# PROC051C_LP_Connector.net
KiCad netlist of a schematic drawn in Altium Designer
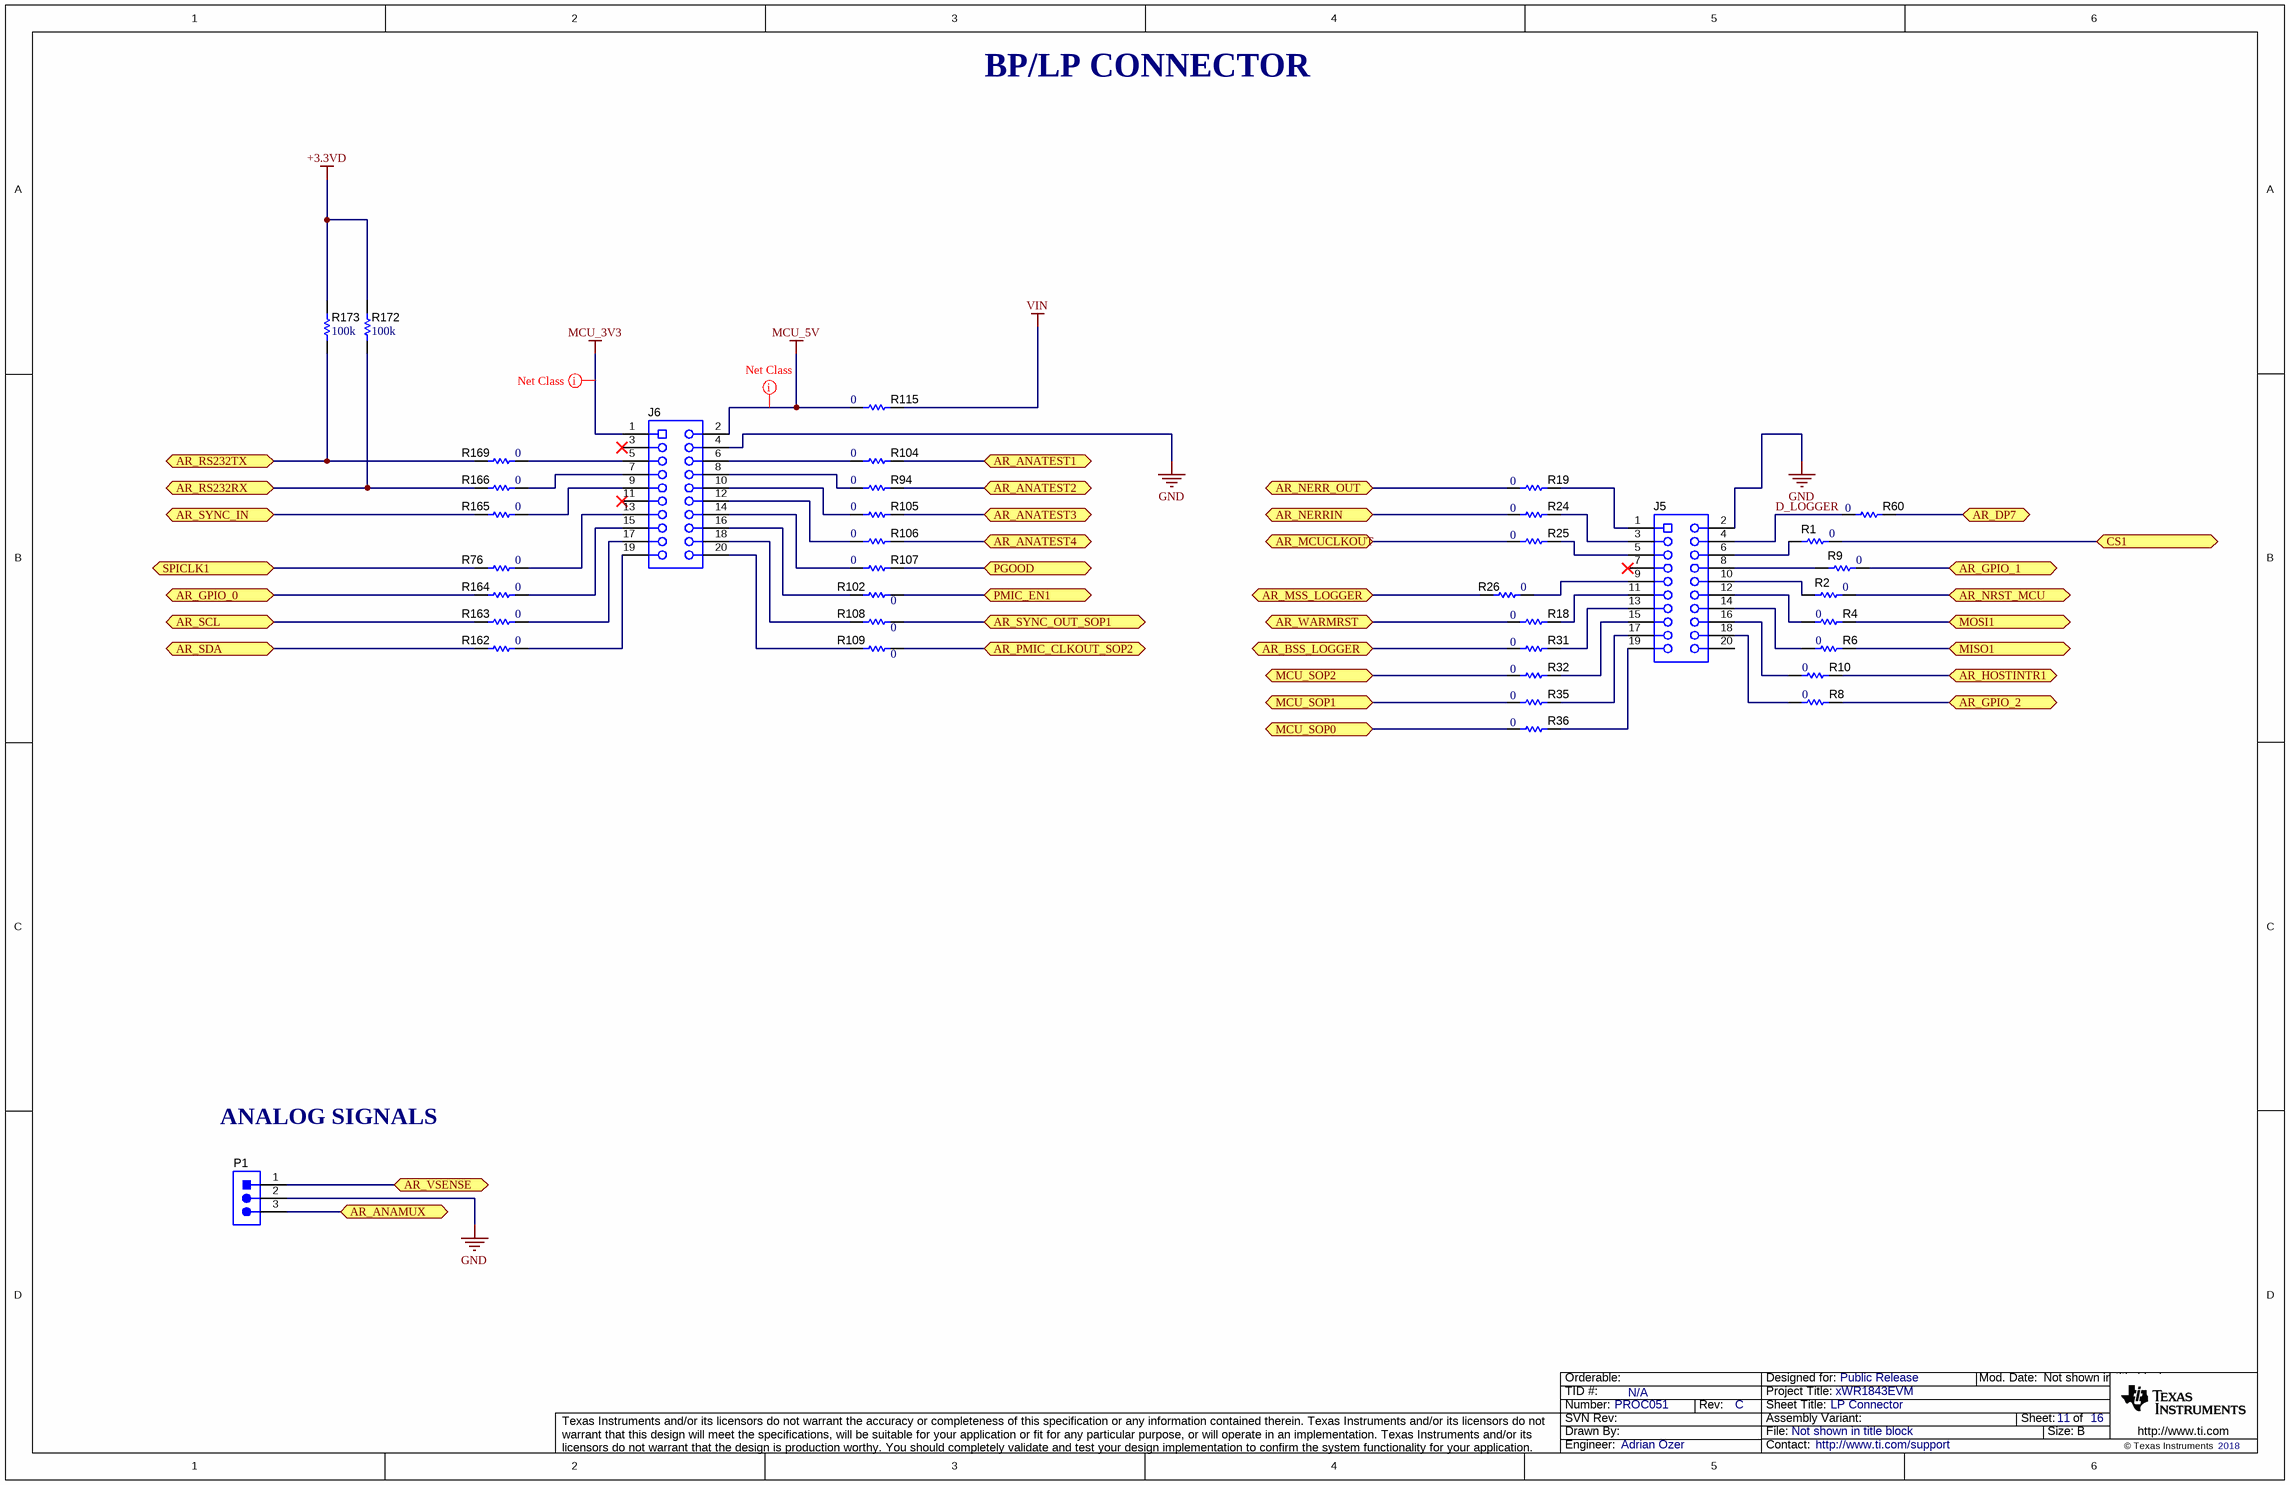
[diagram p0: PROC051C_LP Connector.SchDoc]

(export (version "E")
  (design (tool "Eeschema 10.0.6"))
  (components
    (comp (ref "J5")
      (value "SSM-110-S-DV")
      (footprint "Samtec_SSM-110-x-DV")
      (description "Receptacle, 2.54mm, 10x2, Gold with Tin tail, SMT")
      (fields (field (name "MANUFACTURER") "Samtec"))
      (libsource (lib "Altium Vault - TI") (part "CMP-0078182-1"))
    )
    (comp (ref "J6")
      (value "SSM-110-S-DV")
      (footprint "Samtec_SSM-110-x-DV")
      (description "Receptacle, 2.54mm, 10x2, Gold with Tin tail, SMT")
      (fields (field (name "MANUFACTURER") "Samtec"))
      (libsource (lib "Altium Vault - TI") (part "CMP-0078182-1"))
    )
    (comp (ref "P1")
      (value "TSW-103-07-T-S")
      (footprint "Samtec_TSW-103-07-T-S")
      (description "Header, 2.54 mm, 3x1, Tin, TH")
      (fields (field (name "MANUFACTURER") "Samtec"))
      (libsource (lib "Altium Vault - TI") (part "Header_3x1"))
    )
    (comp (ref "R1")
      (value "CRCW02010000Z0ED")
      (footprint "0201_Silk")
      (description "RES, 0, 5%, 0.05 W, 0201")
      (fields (field (name "MANUFACTURER") "Vishay-Dale") (field (name "VALUEDISPLAYED") "0"))
      (libsource (lib "Altium Vault - TI") (part "Resistor"))
    )
    (comp (ref "R2")
      (value "CRCW02010000Z0ED")
      (footprint "0201_Silk")
      (description "RES, 0, 5%, 0.05 W, 0201")
      (fields (field (name "MANUFACTURER") "Vishay-Dale") (field (name "VALUEDISPLAYED") "0"))
      (libsource (lib "Altium Vault - TI") (part "Resistor"))
    )
    (comp (ref "R4")
      (value "CRCW02010000Z0ED")
      (footprint "0201_Silk")
      (description "RES, 0, 5%, 0.05 W, 0201")
      (fields (field (name "MANUFACTURER") "Vishay-Dale") (field (name "VALUEDISPLAYED") "0"))
      (libsource (lib "Altium Vault - TI") (part "Resistor"))
    )
    (comp (ref "R6")
      (value "CRCW02010000Z0ED")
      (footprint "0201_Silk")
      (description "RES, 0, 5%, 0.05 W, 0201")
      (fields (field (name "MANUFACTURER") "Vishay-Dale") (field (name "VALUEDISPLAYED") "0"))
      (libsource (lib "Altium Vault - TI") (part "Resistor"))
    )
    (comp (ref "R8")
      (value "CRCW02010000Z0ED")
      (footprint "0201_Silk")
      (description "RES, 0, 5%, 0.05 W, 0201")
      (fields (field (name "MANUFACTURER") "Vishay-Dale") (field (name "VALUEDISPLAYED") "0"))
      (libsource (lib "Altium Vault - TI") (part "Resistor"))
    )
    (comp (ref "R9")
      (value "CRCW02010000Z0ED")
      (footprint "0201_Silk")
      (description "RES, 0, 5%, 0.05 W, 0201")
      (fields (field (name "MANUFACTURER") "Vishay-Dale") (field (name "VALUEDISPLAYED") "0"))
      (libsource (lib "Altium Vault - TI") (part "Resistor"))
    )
    (comp (ref "R10")
      (value "CRCW02010000Z0ED")
      (footprint "0201_Silk")
      (description "RES, 0, 5%, 0.05 W, 0201")
      (fields (field (name "MANUFACTURER") "Vishay-Dale") (field (name "VALUEDISPLAYED") "0"))
      (libsource (lib "Altium Vault - TI") (part "Resistor"))
    )
    (comp (ref "R18")
      (value "CRCW02010000Z0ED")
      (footprint "0201_Silk")
      (description "RES, 0, 5%, 0.05 W, 0201")
      (fields (field (name "MANUFACTURER") "Vishay-Dale") (field (name "VALUEDISPLAYED") "0"))
      (libsource (lib "Altium Vault - TI") (part "Resistor"))
    )
    (comp (ref "R19")
      (value "CRCW02010000Z0ED")
      (footprint "0201_Silk")
      (description "RES, 0, 5%, 0.05 W, 0201")
      (fields (field (name "MANUFACTURER") "Vishay-Dale") (field (name "VALUEDISPLAYED") "0"))
      (libsource (lib "Altium Vault - TI") (part "Resistor"))
    )
    (comp (ref "R24")
      (value "CRCW02010000Z0ED")
      (footprint "0201_Silk")
      (description "RES, 0, 5%, 0.05 W, 0201")
      (fields (field (name "MANUFACTURER") "Vishay-Dale") (field (name "VALUEDISPLAYED") "0"))
      (libsource (lib "Altium Vault - TI") (part "Resistor"))
    )
    (comp (ref "R25")
      (value "CRCW02010000Z0ED")
      (footprint "0201_Silk")
      (description "RES, 0, 5%, 0.05 W, 0201")
      (fields (field (name "MANUFACTURER") "Vishay-Dale") (field (name "VALUEDISPLAYED") "0"))
      (libsource (lib "Altium Vault - TI") (part "Resistor"))
    )
    (comp (ref "R26")
      (value "CRCW02010000Z0ED")
      (footprint "0201_Silk")
      (description "RES, 0, 5%, 0.05 W, 0201")
      (fields (field (name "MANUFACTURER") "Vishay-Dale") (field (name "VALUEDISPLAYED") "0"))
      (libsource (lib "Altium Vault - TI") (part "Resistor"))
    )
    (comp (ref "R31")
      (value "CRCW02010000Z0ED")
      (footprint "0201_Silk")
      (description "RES, 0, 5%, 0.05 W, 0201")
      (fields (field (name "MANUFACTURER") "Vishay-Dale") (field (name "VALUEDISPLAYED") "0"))
      (libsource (lib "Altium Vault - TI") (part "Resistor"))
    )
    (comp (ref "R32")
      (value "CRCW02010000Z0ED")
      (footprint "0201_Silk")
      (description "RES, 0, 5%, 0.05 W, 0201")
      (fields (field (name "MANUFACTURER") "Vishay-Dale") (field (name "VALUEDISPLAYED") "0"))
      (libsource (lib "Altium Vault - TI") (part "Resistor"))
    )
    (comp (ref "R35")
      (value "CRCW02010000Z0ED")
      (footprint "0201_Silk")
      (description "RES, 0, 5%, 0.05 W, 0201")
      (fields (field (name "MANUFACTURER") "Vishay-Dale") (field (name "VALUEDISPLAYED") "0"))
      (libsource (lib "Altium Vault - TI") (part "Resistor"))
    )
    (comp (ref "R36")
      (value "CRCW02010000Z0ED")
      (footprint "0201_Silk")
      (description "RES, 0, 5%, 0.05 W, 0201")
      (fields (field (name "MANUFACTURER") "Vishay-Dale") (field (name "VALUEDISPLAYED") "0"))
      (libsource (lib "Altium Vault - TI") (part "Resistor"))
    )
    (comp (ref "R60")
      (value "CRCW02010000Z0ED")
      (footprint "0201_Silk")
      (description "RES, 0, 5%, 0.05 W, 0201")
      (fields (field (name "MANUFACTURER") "Vishay-Dale") (field (name "VALUEDISPLAYED") "0"))
      (libsource (lib "Altium Vault - TI") (part "Resistor"))
    )
    (comp (ref "R76")
      (value "CRCW02010000Z0ED")
      (footprint "0201_Silk")
      (description "RES, 0, 5%, 0.05 W, 0201")
      (fields (field (name "MANUFACTURER") "Vishay-Dale") (field (name "VALUEDISPLAYED") "0"))
      (libsource (lib "Altium Vault - TI") (part "Resistor"))
    )
    (comp (ref "R94")
      (value "CRCW02010000Z0ED")
      (footprint "0201_Silk")
      (description "RES, 0, 5%, 0.05 W, 0201")
      (fields (field (name "MANUFACTURER") "Vishay-Dale") (field (name "VALUEDISPLAYED") "0"))
      (libsource (lib "Altium Vault - TI") (part "Resistor"))
    )
    (comp (ref "R102")
      (value "CRCW02010000Z0ED")
      (footprint "0201_Silk")
      (description "RES, 0, 5%, 0.05 W, 0201")
      (fields (field (name "MANUFACTURER") "Vishay-Dale") (field (name "VALUEDISPLAYED") "0"))
      (libsource (lib "Altium Vault - TI") (part "Resistor"))
    )
    (comp (ref "R104")
      (value "CRCW02010000Z0ED")
      (footprint "0201_Silk")
      (description "RES, 0, 5%, 0.05 W, 0201")
      (fields (field (name "MANUFACTURER") "Vishay-Dale") (field (name "VALUEDISPLAYED") "0"))
      (libsource (lib "Altium Vault - TI") (part "Resistor"))
    )
    (comp (ref "R105")
      (value "CRCW02010000Z0ED")
      (footprint "0201_Silk")
      (description "RES, 0, 5%, 0.05 W, 0201")
      (fields (field (name "MANUFACTURER") "Vishay-Dale") (field (name "VALUEDISPLAYED") "0"))
      (libsource (lib "Altium Vault - TI") (part "Resistor"))
    )
    (comp (ref "R106")
      (value "CRCW02010000Z0ED")
      (footprint "0201_Silk")
      (description "RES, 0, 5%, 0.05 W, 0201")
      (fields (field (name "MANUFACTURER") "Vishay-Dale") (field (name "VALUEDISPLAYED") "0"))
      (libsource (lib "Altium Vault - TI") (part "Resistor"))
    )
    (comp (ref "R107")
      (value "ERJ-2GE0R00X")
      (footprint "0402L")
      (description "RES, 0, 5%, 0.1 W, AEC-Q200 Grade 0, 0402")
      (fields (field (name "MANUFACTURER") "Panasonic") (field (name "VALUEDISPLAYED") "0"))
      (libsource (lib "Altium Vault - TI") (part "Resistor"))
    )
    (comp (ref "R108")
      (value "CRCW02010000Z0ED")
      (footprint "0201_Silk")
      (description "RES, 0, 5%, 0.05 W, 0201")
      (fields (field (name "MANUFACTURER") "Vishay-Dale") (field (name "VALUEDISPLAYED") "0"))
      (libsource (lib "Altium Vault - TI") (part "Resistor"))
    )
    (comp (ref "R109")
      (value "CRCW02010000Z0ED")
      (footprint "0201_Silk")
      (description "RES, 0, 5%, 0.05 W, 0201")
      (fields (field (name "MANUFACTURER") "Vishay-Dale") (field (name "VALUEDISPLAYED") "0"))
      (libsource (lib "Altium Vault - TI") (part "Resistor"))
    )
    (comp (ref "R115")
      (value "CRCW20100000Z0EF")
      (footprint "2010")
      (description "RES, 0, 5%, 0.75 W, AEC-Q200 Grade 0, 2010")
      (fields (field (name "MANUFACTURER") "Vishay-Dale") (field (name "VALUEDISPLAYED") "0"))
      (libsource (lib "Altium Vault - TI") (part "Resistor"))
    )
    (comp (ref "R162")
      (value "CRCW02010000Z0ED")
      (footprint "0201_Silk")
      (description "RES, 0, 5%, 0.05 W, 0201")
      (fields (field (name "MANUFACTURER") "Vishay-Dale") (field (name "VALUEDISPLAYED") "0"))
      (libsource (lib "Altium Vault - TI") (part "Resistor"))
    )
    (comp (ref "R163")
      (value "CRCW02010000Z0ED")
      (footprint "0201_Silk")
      (description "RES, 0, 5%, 0.05 W, 0201")
      (fields (field (name "MANUFACTURER") "Vishay-Dale") (field (name "VALUEDISPLAYED") "0"))
      (libsource (lib "Altium Vault - TI") (part "Resistor"))
    )
    (comp (ref "R164")
      (value "CRCW02010000Z0ED")
      (footprint "0201_Silk")
      (description "RES, 0, 5%, 0.05 W, 0201")
      (fields (field (name "MANUFACTURER") "Vishay-Dale") (field (name "VALUEDISPLAYED") "0"))
      (libsource (lib "Altium Vault - TI") (part "Resistor"))
    )
    (comp (ref "R165")
      (value "CRCW02010000Z0ED")
      (footprint "0201_Silk")
      (description "RES, 0, 5%, 0.05 W, 0201")
      (fields (field (name "MANUFACTURER") "Vishay-Dale") (field (name "VALUEDISPLAYED") "0"))
      (libsource (lib "Altium Vault - TI") (part "Resistor"))
    )
    (comp (ref "R166")
      (value "CRCW02010000Z0ED")
      (footprint "0201_Silk")
      (description "RES, 0, 5%, 0.05 W, 0201")
      (fields (field (name "MANUFACTURER") "Vishay-Dale") (field (name "VALUEDISPLAYED") "0"))
      (libsource (lib "Altium Vault - TI") (part "Resistor"))
    )
    (comp (ref "R169")
      (value "CRCW02010000Z0ED")
      (footprint "0201_Silk")
      (description "RES, 0, 5%, 0.05 W, 0201")
      (fields (field (name "MANUFACTURER") "Vishay-Dale") (field (name "VALUEDISPLAYED") "0"))
      (libsource (lib "Altium Vault - TI") (part "Resistor"))
    )
    (comp (ref "R172")
      (value "CRCW0402100KFKED")
      (footprint "0402L")
      (description "RES, 100 k, 1%, 0.063 W, AEC-Q200 Grade 0, 0402")
      (fields (field (name "MANUFACTURER") "Vishay-Dale") (field (name "VALUEDISPLAYED") "100k"))
      (libsource (lib "Altium Vault - TI") (part "Resistor"))
    )
    (comp (ref "R173")
      (value "CRCW0402100KFKED")
      (footprint "0402L")
      (description "RES, 100 k, 1%, 0.063 W, AEC-Q200 Grade 0, 0402")
      (fields (field (name "MANUFACTURER") "Vishay-Dale") (field (name "VALUEDISPLAYED") "100k"))
      (libsource (lib "Altium Vault - TI") (part "Resistor"))
    )
  )
  (nets
    (net (code "1") (name "+3.3VD") (class "Default")
      (node (ref "R172") (pin "2") (pinfunction "2_2") (pintype "passive"))
      (node (ref "R173") (pin "2") (pinfunction "2_2") (pintype "passive"))
    )
    (net (code "2") (name "/AR_ANAMUX") (class "Default")
      (node (ref "P1") (pin "3") (pinfunction "3_3") (pintype "passive"))
    )
    (net (code "3") (name "/AR_ANATEST1") (class "Default")
      (node (ref "R104") (pin "2") (pinfunction "2_2") (pintype "passive"))
    )
    (net (code "4") (name "/AR_ANATEST2") (class "Default")
      (node (ref "R94") (pin "2") (pinfunction "2_2") (pintype "passive"))
    )
    (net (code "5") (name "/AR_ANATEST3") (class "Default")
      (node (ref "R105") (pin "2") (pinfunction "2_2") (pintype "passive"))
    )
    (net (code "6") (name "/AR_ANATEST4") (class "Default")
      (node (ref "R106") (pin "2") (pinfunction "2_2") (pintype "passive"))
    )
    (net (code "7") (name "/AR_BSS_LOGGER") (class "Default")
      (node (ref "R31") (pin "1") (pinfunction "1_1") (pintype "passive"))
    )
    (net (code "8") (name "/AR_DP7") (class "Default")
      (node (ref "R60") (pin "2") (pinfunction "2_2") (pintype "passive"))
    )
    (net (code "9") (name "/AR_GPIO_0") (class "Default")
      (node (ref "R164") (pin "1") (pinfunction "1_1") (pintype "passive"))
    )
    (net (code "10") (name "/AR_GPIO_1") (class "Default")
      (node (ref "R9") (pin "2") (pinfunction "2_2") (pintype "passive"))
    )
    (net (code "11") (name "/AR_GPIO_2") (class "Default")
      (node (ref "R8") (pin "2") (pinfunction "2_2") (pintype "passive"))
    )
    (net (code "12") (name "/AR_HOSTINTR1") (class "Default")
      (node (ref "R10") (pin "2") (pinfunction "2_2") (pintype "passive"))
    )
    (net (code "13") (name "/AR_MCUCLKOUT") (class "Default")
      (node (ref "R25") (pin "1") (pinfunction "1_1") (pintype "passive"))
    )
    (net (code "14") (name "/AR_MSS_LOGGER") (class "Default")
      (node (ref "R26") (pin "1") (pinfunction "1_1") (pintype "passive"))
    )
    (net (code "15") (name "/AR_NERRIN") (class "Default")
      (node (ref "R24") (pin "1") (pinfunction "1_1") (pintype "passive"))
    )
    (net (code "16") (name "/AR_NERR_OUT") (class "Default")
      (node (ref "R19") (pin "1") (pinfunction "1_1") (pintype "passive"))
    )
    (net (code "17") (name "/AR_NRST_MCU") (class "Default")
      (node (ref "R2") (pin "2") (pinfunction "2_2") (pintype "passive"))
    )
    (net (code "18") (name "/AR_PMIC_CLKOUT_SOP2") (class "Default")
      (node (ref "R109") (pin "2") (pinfunction "2_2") (pintype "passive"))
    )
    (net (code "19") (name "/AR_RS232RX") (class "Default")
      (node (ref "R166") (pin "1") (pinfunction "1_1") (pintype "passive"))
      (node (ref "R172") (pin "1") (pinfunction "1_1") (pintype "passive"))
    )
    (net (code "20") (name "/AR_RS232TX") (class "Default")
      (node (ref "R169") (pin "1") (pinfunction "1_1") (pintype "passive"))
      (node (ref "R173") (pin "1") (pinfunction "1_1") (pintype "passive"))
    )
    (net (code "21") (name "/AR_SCL") (class "Default")
      (node (ref "R163") (pin "1") (pinfunction "1_1") (pintype "passive"))
    )
    (net (code "22") (name "/AR_SDA") (class "Default")
      (node (ref "R162") (pin "1") (pinfunction "1_1") (pintype "passive"))
    )
    (net (code "23") (name "/AR_SYNC_IN") (class "Default")
      (node (ref "R165") (pin "1") (pinfunction "1_1") (pintype "passive"))
    )
    (net (code "24") (name "/AR_SYNC_OUT_SOP1") (class "Default")
      (node (ref "R108") (pin "2") (pinfunction "2_2") (pintype "passive"))
    )
    (net (code "25") (name "/AR_VSENSE") (class "Default")
      (node (ref "P1") (pin "1") (pinfunction "1_1") (pintype "passive"))
    )
    (net (code "26") (name "/AR_WARMRST") (class "Default")
      (node (ref "R18") (pin "1") (pinfunction "1_1") (pintype "passive"))
    )
    (net (code "27") (name "/CS1") (class "Default")
      (node (ref "R1") (pin "2") (pinfunction "2_2") (pintype "passive"))
    )
    (net (code "28") (name "/D_LOGGER") (class "Default")
      (node (ref "J5") (pin "4") (pinfunction "4_4") (pintype "passive"))
      (node (ref "R60") (pin "1") (pinfunction "1_1") (pintype "passive"))
    )
    (net (code "29") (name "/MCU_SOP0") (class "Default")
      (node (ref "R36") (pin "1") (pinfunction "1_1") (pintype "passive"))
    )
    (net (code "30") (name "/MCU_SOP1") (class "Default")
      (node (ref "R35") (pin "1") (pinfunction "1_1") (pintype "passive"))
    )
    (net (code "31") (name "/MCU_SOP2") (class "Default")
      (node (ref "R32") (pin "1") (pinfunction "1_1") (pintype "passive"))
    )
    (net (code "32") (name "/MISO1") (class "Default")
      (node (ref "R6") (pin "2") (pinfunction "2_2") (pintype "passive"))
    )
    (net (code "33") (name "/MOSI1") (class "Default")
      (node (ref "R4") (pin "2") (pinfunction "2_2") (pintype "passive"))
    )
    (net (code "34") (name "/PGOOD") (class "Default")
      (node (ref "R107") (pin "2") (pinfunction "2_2") (pintype "passive"))
    )
    (net (code "35") (name "/PMIC_EN1") (class "Default")
      (node (ref "R102") (pin "2") (pinfunction "2_2") (pintype "passive"))
    )
    (net (code "36") (name "/SPICLK1") (class "Default")
      (node (ref "R76") (pin "1") (pinfunction "1_1") (pintype "passive"))
    )
    (net (code "37") (name "GND") (class "Default")
      (node (ref "J5") (pin "2") (pinfunction "2_2") (pintype "passive"))
      (node (ref "J6") (pin "4") (pinfunction "4_4") (pintype "passive"))
      (node (ref "P1") (pin "2") (pinfunction "2_2") (pintype "passive"))
    )
    (net (code "38") (name "MCU_3V3") (class "Default")
      (node (ref "J6") (pin "1") (pinfunction "1_1") (pintype "passive"))
    )
    (net (code "39") (name "MCU_5V") (class "Default")
      (node (ref "J6") (pin "2") (pinfunction "2_2") (pintype "passive"))
      (node (ref "R115") (pin "1") (pinfunction "1_1") (pintype "passive"))
    )
    (net (code "40") (name "Net-(J5-Pad1)") (class "Default")
      (node (ref "J5") (pin "1") (pinfunction "1_1") (pintype "passive"))
      (node (ref "R19") (pin "2") (pinfunction "2_2") (pintype "passive"))
    )
    (net (code "41") (name "Net-(J5-Pad3)") (class "Default")
      (node (ref "J5") (pin "3") (pinfunction "3_3") (pintype "passive"))
      (node (ref "R24") (pin "2") (pinfunction "2_2") (pintype "passive"))
    )
    (net (code "42") (name "Net-(J5-Pad5)") (class "Default")
      (node (ref "J5") (pin "5") (pinfunction "5_5") (pintype "passive"))
      (node (ref "R25") (pin "2") (pinfunction "2_2") (pintype "passive"))
    )
    (net (code "43") (name "Net-(J5-Pad6)") (class "Default")
      (node (ref "J5") (pin "6") (pinfunction "6_6") (pintype "passive"))
      (node (ref "R1") (pin "1") (pinfunction "1_1") (pintype "passive"))
    )
    (net (code "44") (name "Net-(J5-Pad8)") (class "Default")
      (node (ref "J5") (pin "8") (pinfunction "8_8") (pintype "passive"))
      (node (ref "R9") (pin "1") (pinfunction "1_1") (pintype "passive"))
    )
    (net (code "45") (name "Net-(J5-Pad9)") (class "Default")
      (node (ref "J5") (pin "9") (pinfunction "9_9") (pintype "passive"))
      (node (ref "R26") (pin "2") (pinfunction "2_2") (pintype "passive"))
    )
    (net (code "46") (name "Net-(J5-Pad10)") (class "Default")
      (node (ref "J5") (pin "10") (pinfunction "10_10") (pintype "passive"))
      (node (ref "R2") (pin "1") (pinfunction "1_1") (pintype "passive"))
    )
    (net (code "47") (name "Net-(J5-Pad11)") (class "Default")
      (node (ref "J5") (pin "11") (pinfunction "11_11") (pintype "passive"))
      (node (ref "R18") (pin "2") (pinfunction "2_2") (pintype "passive"))
    )
    (net (code "48") (name "Net-(J5-Pad12)") (class "Default")
      (node (ref "J5") (pin "12") (pinfunction "12_12") (pintype "passive"))
      (node (ref "R4") (pin "1") (pinfunction "1_1") (pintype "passive"))
    )
    (net (code "49") (name "Net-(J5-Pad13)") (class "Default")
      (node (ref "J5") (pin "13") (pinfunction "13_13") (pintype "passive"))
      (node (ref "R31") (pin "2") (pinfunction "2_2") (pintype "passive"))
    )
    (net (code "50") (name "Net-(J5-Pad14)") (class "Default")
      (node (ref "J5") (pin "14") (pinfunction "14_14") (pintype "passive"))
      (node (ref "R6") (pin "1") (pinfunction "1_1") (pintype "passive"))
    )
    (net (code "51") (name "Net-(J5-Pad15)") (class "Default")
      (node (ref "J5") (pin "15") (pinfunction "15_15") (pintype "passive"))
      (node (ref "R32") (pin "2") (pinfunction "2_2") (pintype "passive"))
    )
    (net (code "52") (name "Net-(J5-Pad16)") (class "Default")
      (node (ref "J5") (pin "16") (pinfunction "16_16") (pintype "passive"))
      (node (ref "R10") (pin "1") (pinfunction "1_1") (pintype "passive"))
    )
    (net (code "53") (name "Net-(J5-Pad17)") (class "Default")
      (node (ref "J5") (pin "17") (pinfunction "17_17") (pintype "passive"))
      (node (ref "R35") (pin "2") (pinfunction "2_2") (pintype "passive"))
    )
    (net (code "54") (name "Net-(J5-Pad18)") (class "Default")
      (node (ref "J5") (pin "18") (pinfunction "18_18") (pintype "passive"))
      (node (ref "R8") (pin "1") (pinfunction "1_1") (pintype "passive"))
    )
    (net (code "55") (name "Net-(J5-Pad19)") (class "Default")
      (node (ref "J5") (pin "19") (pinfunction "19_19") (pintype "passive"))
      (node (ref "R36") (pin "2") (pinfunction "2_2") (pintype "passive"))
    )
    (net (code "56") (name "Net-(J6-Pad5)") (class "Default")
      (node (ref "J6") (pin "5") (pinfunction "5_5") (pintype "passive"))
      (node (ref "R169") (pin "2") (pinfunction "2_2") (pintype "passive"))
    )
    (net (code "57") (name "Net-(J6-Pad6)") (class "Default")
      (node (ref "J6") (pin "6") (pinfunction "6_6") (pintype "passive"))
      (node (ref "R104") (pin "1") (pinfunction "1_1") (pintype "passive"))
    )
    (net (code "58") (name "Net-(J6-Pad7)") (class "Default")
      (node (ref "J6") (pin "7") (pinfunction "7_7") (pintype "passive"))
      (node (ref "R166") (pin "2") (pinfunction "2_2") (pintype "passive"))
    )
    (net (code "59") (name "Net-(J6-Pad8)") (class "Default")
      (node (ref "J6") (pin "8") (pinfunction "8_8") (pintype "passive"))
      (node (ref "R94") (pin "1") (pinfunction "1_1") (pintype "passive"))
    )
    (net (code "60") (name "Net-(J6-Pad9)") (class "Default")
      (node (ref "J6") (pin "9") (pinfunction "9_9") (pintype "passive"))
      (node (ref "R165") (pin "2") (pinfunction "2_2") (pintype "passive"))
    )
    (net (code "61") (name "Net-(J6-Pad10)") (class "Default")
      (node (ref "J6") (pin "10") (pinfunction "10_10") (pintype "passive"))
      (node (ref "R105") (pin "1") (pinfunction "1_1") (pintype "passive"))
    )
    (net (code "62") (name "Net-(J6-Pad12)") (class "Default")
      (node (ref "J6") (pin "12") (pinfunction "12_12") (pintype "passive"))
      (node (ref "R106") (pin "1") (pinfunction "1_1") (pintype "passive"))
    )
    (net (code "63") (name "Net-(J6-Pad13)") (class "Default")
      (node (ref "J6") (pin "13") (pinfunction "13_13") (pintype "passive"))
      (node (ref "R76") (pin "2") (pinfunction "2_2") (pintype "passive"))
    )
    (net (code "64") (name "Net-(J6-Pad14)") (class "Default")
      (node (ref "J6") (pin "14") (pinfunction "14_14") (pintype "passive"))
      (node (ref "R107") (pin "1") (pinfunction "1_1") (pintype "passive"))
    )
    (net (code "65") (name "Net-(J6-Pad15)") (class "Default")
      (node (ref "J6") (pin "15") (pinfunction "15_15") (pintype "passive"))
      (node (ref "R164") (pin "2") (pinfunction "2_2") (pintype "passive"))
    )
    (net (code "66") (name "Net-(J6-Pad16)") (class "Default")
      (node (ref "J6") (pin "16") (pinfunction "16_16") (pintype "passive"))
      (node (ref "R102") (pin "1") (pinfunction "1_1") (pintype "passive"))
    )
    (net (code "67") (name "Net-(J6-Pad17)") (class "Default")
      (node (ref "J6") (pin "17") (pinfunction "17_17") (pintype "passive"))
      (node (ref "R163") (pin "2") (pinfunction "2_2") (pintype "passive"))
    )
    (net (code "68") (name "Net-(J6-Pad18)") (class "Default")
      (node (ref "J6") (pin "18") (pinfunction "18_18") (pintype "passive"))
      (node (ref "R108") (pin "1") (pinfunction "1_1") (pintype "passive"))
    )
    (net (code "69") (name "Net-(J6-Pad19)") (class "Default")
      (node (ref "J6") (pin "19") (pinfunction "19_19") (pintype "passive"))
      (node (ref "R162") (pin "2") (pinfunction "2_2") (pintype "passive"))
    )
    (net (code "70") (name "Net-(J6-Pad20)") (class "Default")
      (node (ref "J6") (pin "20") (pinfunction "20_20") (pintype "passive"))
      (node (ref "R109") (pin "1") (pinfunction "1_1") (pintype "passive"))
    )
    (net (code "71") (name "VIN") (class "Default")
      (node (ref "R115") (pin "2") (pinfunction "2_2") (pintype "passive"))
    )
    (net (code "72") (name "unconnected-(J5-Pad7)") (class "Default")
      (node (ref "J5") (pin "7") (pinfunction "7_7") (pintype "passive+no_connect"))
    )
    (net (code "73") (name "unconnected-(J5-Pad20)") (class "Default")
      (node (ref "J5") (pin "20") (pinfunction "20_20") (pintype "passive"))
    )
    (net (code "74") (name "unconnected-(J6-Pad3)") (class "Default")
      (node (ref "J6") (pin "3") (pinfunction "3_3") (pintype "passive+no_connect"))
    )
    (net (code "75") (name "unconnected-(J6-Pad11)") (class "Default")
      (node (ref "J6") (pin "11") (pinfunction "11_11") (pintype "passive+no_connect"))
    )
  )
)
